# Linear_array.net
KiCad netlist of a schematic drawn in Altium Designer
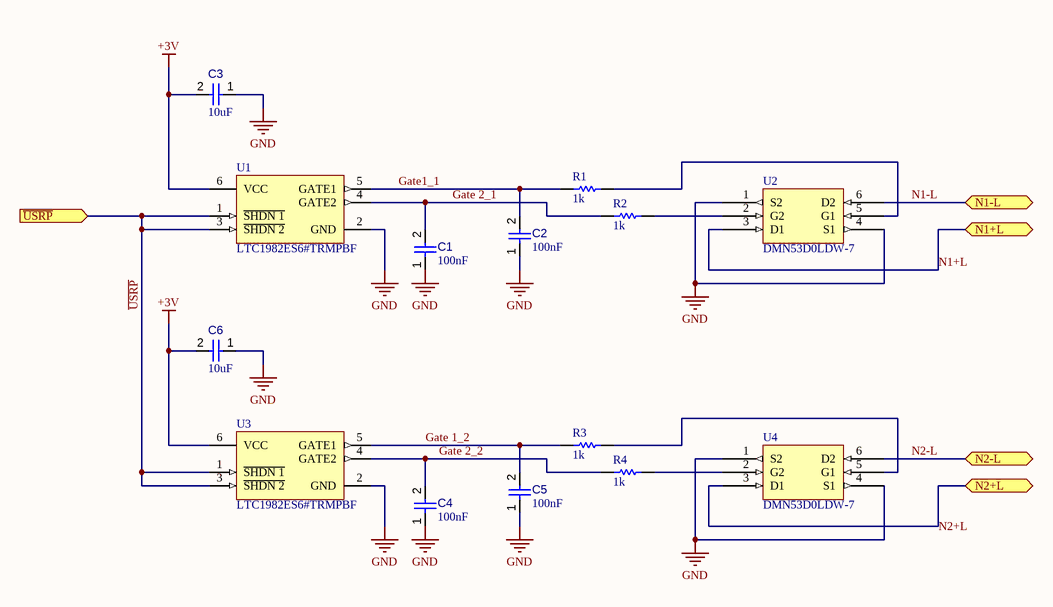
[diagram p0: Linear array.SchDoc]

(export (version "E")
  (design (tool "Eeschema 10.0.6"))
  (components
    (comp (ref "C1")
      (value "100nF")
      (footprint "CAPC1608X90X40NL10T20")
      (description "Chip Capacitor, 100 nF, +/- 10%, 50 V, 0603 (1608 Metric)")
      (fields (field (name "TOLERANCE") "10%") (field (name "Comment") "Capacitor 100 nF +/-10% 50 V 0603"))
      (libsource (lib "Nick") (part "CAP-NP-2"))
    )
    (comp (ref "C2")
      (value "100nF")
      (footprint "CAPC1608X90X40NL10T20")
      (description "Chip Capacitor, 100 nF, +/- 10%, 50 V, 0603 (1608 Metric)")
      (fields (field (name "TOLERANCE") "10%") (field (name "Comment") "Capacitor 100 nF +/-10% 50 V 0603"))
      (libsource (lib "Nick") (part "CAP-NP-2"))
    )
    (comp (ref "C3")
      (value "10uF")
      (footprint "CAPC1608X90X40NL10T20")
      (description "Chip Capacitor, 100 nF, +/- 10%, 50 V, 0603 (1608 Metric)")
      (fields (field (name "TOLERANCE") "10%") (field (name "Comment") "Capacitor 100 nF +/-10% 50 V 0603"))
      (libsource (lib "Nick") (part "CAP-NP-2"))
    )
    (comp (ref "C4")
      (value "100nF")
      (footprint "CAPC1608X90X40NL10T20")
      (description "Chip Capacitor, 100 nF, +/- 10%, 50 V, 0603 (1608 Metric)")
      (fields (field (name "TOLERANCE") "10%") (field (name "Comment") "Capacitor 100 nF +/-10% 50 V 0603"))
      (libsource (lib "Nick") (part "CAP-NP-2"))
    )
    (comp (ref "C5")
      (value "100nF")
      (footprint "CAPC1608X90X40NL10T20")
      (description "Chip Capacitor, 100 nF, +/- 10%, 50 V, 0603 (1608 Metric)")
      (fields (field (name "TOLERANCE") "10%") (field (name "Comment") "Capacitor 100 nF +/-10% 50 V 0603"))
      (libsource (lib "Nick") (part "CAP-NP-2"))
    )
    (comp (ref "C6")
      (value "10uF")
      (footprint "CAPC1608X90X40NL10T20")
      (description "Chip Capacitor, 100 nF, +/- 10%, 50 V, 0603 (1608 Metric)")
      (fields (field (name "TOLERANCE") "10%") (field (name "Comment") "Capacitor 100 nF +/-10% 50 V 0603"))
      (libsource (lib "Nick") (part "CAP-NP-2"))
    )
    (comp (ref "R1")
      (value "1k")
      (description "Resistor")
      (libsource (lib "Simulation Generic Components") (part "Resistor"))
    )
    (comp (ref "R2")
      (value "1k")
      (description "Resistor")
      (libsource (lib "Simulation Generic Components") (part "Resistor"))
    )
    (comp (ref "R3")
      (value "1k")
      (description "Resistor")
      (libsource (lib "Simulation Generic Components") (part "Resistor"))
    )
    (comp (ref "R4")
      (value "1k")
      (description "Resistor")
      (libsource (lib "Simulation Generic Components") (part "Resistor"))
    )
    (comp (ref "U1")
      (value "LTC1982ES6#TRMPBF")
      (footprint "LT-S6-6-SOT-23_M")
      (fields (field (name "MANUFACTURER") "Linear Technology"))
      (libsource (lib "Altium Content Vault") (part "LT-LTC1982-S6-6"))
    )
    (comp (ref "U2")
      (value "DMN53D0LDW-7")
      (footprint "SOT95P285X130-6N")
      (description "Transistor MOSFET Array Dual N-CH 50V 360mA 3-Pin SOT-363 T/R")
      (libsource (lib "Nick") (part "DMN2004DMK-7-Symbol-1"))
    )
    (comp (ref "U3")
      (value "LTC1982ES6#TRMPBF")
      (footprint "LT-S6-6-SOT-23_M")
      (fields (field (name "MANUFACTURER") "Linear Technology"))
      (libsource (lib "Altium Content Vault") (part "LT-LTC1982-S6-6"))
    )
    (comp (ref "U4")
      (value "DMN53D0LDW-7")
      (footprint "SOT95P285X130-6N")
      (description "Transistor MOSFET Array Dual N-CH 50V 360mA 3-Pin SOT-363 T/R")
      (libsource (lib "Nick") (part "DMN2004DMK-7-Symbol-1"))
    )
  )
  (nets
    (net (code "1") (name "+3V") (class "Default")
      (node (ref "C3") (pin "2") (pinfunction "2_2") (pintype "passive"))
      (node (ref "C6") (pin "2") (pinfunction "2_2") (pintype "passive"))
      (node (ref "U1") (pin "6") (pinfunction "VCC_6") (pintype "power_in"))
      (node (ref "U3") (pin "6") (pinfunction "VCC_6") (pintype "power_in"))
    )
    (net (code "2") (name "/Gate 1_2") (class "Default")
      (node (ref "C5") (pin "2") (pinfunction "2_2") (pintype "passive"))
      (node (ref "R3") (pin "2") (pinfunction "2_2") (pintype "passive"))
      (node (ref "U3") (pin "5") (pinfunction "GATE1_5") (pintype "output"))
    )
    (net (code "3") (name "/Gate 2_1") (class "Default")
      (node (ref "C1") (pin "2") (pinfunction "2_2") (pintype "passive"))
      (node (ref "R2") (pin "2") (pinfunction "2_2") (pintype "passive"))
      (node (ref "U1") (pin "4") (pinfunction "GATE2_4") (pintype "output"))
    )
    (net (code "4") (name "/Gate 2_2") (class "Default")
      (node (ref "C4") (pin "2") (pinfunction "2_2") (pintype "passive"))
      (node (ref "R4") (pin "2") (pinfunction "2_2") (pintype "passive"))
      (node (ref "U3") (pin "4") (pinfunction "GATE2_4") (pintype "output"))
    )
    (net (code "5") (name "/Gate1_1") (class "Default")
      (node (ref "C2") (pin "2") (pinfunction "2_2") (pintype "passive"))
      (node (ref "R1") (pin "2") (pinfunction "2_2") (pintype "passive"))
      (node (ref "U1") (pin "5") (pinfunction "GATE1_5") (pintype "output"))
    )
    (net (code "6") (name "/N1+L") (class "Default")
      (node (ref "U2") (pin "3") (pinfunction "D1_3") (pintype "input"))
    )
    (net (code "7") (name "/N1-L") (class "Default")
      (node (ref "U2") (pin "6") (pinfunction "D2_6") (pintype "input"))
    )
    (net (code "8") (name "/N2+L") (class "Default")
      (node (ref "U4") (pin "3") (pinfunction "D1_3") (pintype "input"))
    )
    (net (code "9") (name "/N2-L") (class "Default")
      (node (ref "U4") (pin "6") (pinfunction "D2_6") (pintype "input"))
    )
    (net (code "10") (name "/~{USRP}") (class "Default")
      (node (ref "U1") (pin "1") (pinfunction "~{SHDN_1}_1") (pintype "input"))
      (node (ref "U1") (pin "3") (pinfunction "~{SHDN_2}_3") (pintype "input"))
      (node (ref "U3") (pin "1") (pinfunction "~{SHDN_1}_1") (pintype "input"))
      (node (ref "U3") (pin "3") (pinfunction "~{SHDN_2}_3") (pintype "input"))
    )
    (net (code "11") (name "GND") (class "Default")
      (node (ref "C1") (pin "1") (pinfunction "1_1") (pintype "passive"))
      (node (ref "C2") (pin "1") (pinfunction "1_1") (pintype "passive"))
      (node (ref "C3") (pin "1") (pinfunction "1_1") (pintype "passive"))
      (node (ref "C4") (pin "1") (pinfunction "1_1") (pintype "passive"))
      (node (ref "C5") (pin "1") (pinfunction "1_1") (pintype "passive"))
      (node (ref "C6") (pin "1") (pinfunction "1_1") (pintype "passive"))
      (node (ref "U1") (pin "2") (pinfunction "GND_2") (pintype "power_in"))
      (node (ref "U2") (pin "1") (pinfunction "S2_1") (pintype "output"))
      (node (ref "U2") (pin "4") (pinfunction "S1_4") (pintype "output"))
      (node (ref "U3") (pin "2") (pinfunction "GND_2") (pintype "power_in"))
      (node (ref "U4") (pin "1") (pinfunction "S2_1") (pintype "output"))
      (node (ref "U4") (pin "4") (pinfunction "S1_4") (pintype "output"))
    )
    (net (code "12") (name "Net-(U2-G1)") (class "Default")
      (node (ref "R1") (pin "1") (pinfunction "1_1") (pintype "passive"))
      (node (ref "U2") (pin "5") (pinfunction "G1_5") (pintype "input"))
    )
    (net (code "13") (name "Net-(U2-G2)") (class "Default")
      (node (ref "R2") (pin "1") (pinfunction "1_1") (pintype "passive"))
      (node (ref "U2") (pin "2") (pinfunction "G2_2") (pintype "input"))
    )
    (net (code "14") (name "Net-(U4-G1)") (class "Default")
      (node (ref "R3") (pin "1") (pinfunction "1_1") (pintype "passive"))
      (node (ref "U4") (pin "5") (pinfunction "G1_5") (pintype "input"))
    )
    (net (code "15") (name "Net-(U4-G2)") (class "Default")
      (node (ref "R4") (pin "1") (pinfunction "1_1") (pintype "passive"))
      (node (ref "U4") (pin "2") (pinfunction "G2_2") (pintype "input"))
    )
  )
)
